# Thermocouple_Amplifier.net
KiCad netlist of a schematic drawn in Altium Designer
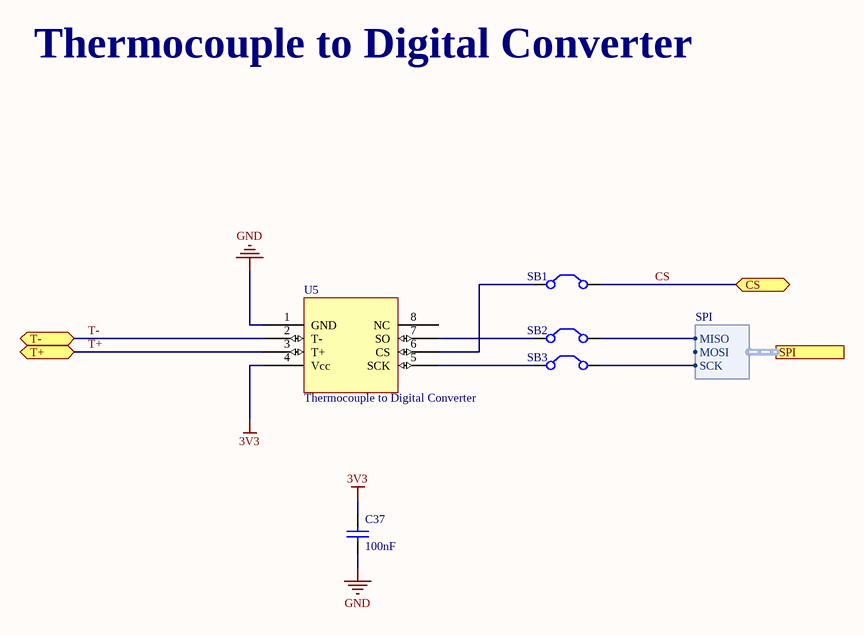
[diagram p0: Thermocouple_Amplifier.SchDoc]

(export (version "E")
  (design (tool "Eeschema 10.0.6"))
  (components
    (comp (ref "C37")
      (value "100nF")
      (footprint "CAP_0603")
      (description "Capacitor")
      (fields (field (name "Comment") "Cap"))
      (libsource (lib "Miscellaneous Devices") (part "Cap"))
    )
    (comp (ref "SB1")
      (value "Solder Bridge")
      (footprint "Solder Bridge")
      (description "Jumper Wire")
      (libsource (lib "Miscellaneous Devices") (part "Jumper"))
    )
    (comp (ref "SB2")
      (value "Solder Bridge")
      (footprint "Solder Bridge")
      (description "Jumper Wire")
      (libsource (lib "Miscellaneous Devices") (part "Jumper"))
    )
    (comp (ref "SB3")
      (value "Solder Bridge")
      (footprint "Solder Bridge")
      (description "Jumper Wire")
      (libsource (lib "Miscellaneous Devices") (part "Jumper"))
    )
    (comp (ref "U5")
      (value "Thermocouple to Digital Converter")
      (footprint "8-SOIC MAXIM")
      (libsource (lib "LaunchyRIOComponents") (part "MAX31855x"))
    )
  )
  (nets
    (net (code "2") (name "/CS") (class "Default")
      (node (ref "SB1") (pin "2") (pinfunction "C2_2") (pintype "passive"))
    )
    (net (code "3") (name "/MISO") (class "Default")
      (node (ref "SB2") (pin "2") (pinfunction "C2_2") (pintype "passive"))
    )
    (net (code "4") (name "/SCK") (class "Default")
      (node (ref "SB3") (pin "2") (pinfunction "C2_2") (pintype "passive"))
    )
    (net (code "5") (name "/T+") (class "Default")
      (node (ref "U5") (pin "3") (pinfunction "T+_3") (pintype "bidirectional"))
    )
    (net (code "6") (name "/T-") (class "Default")
      (node (ref "U5") (pin "2") (pinfunction "T-_2") (pintype "bidirectional"))
    )
    (net (code "8") (name "3V3") (class "Default")
      (node (ref "C37") (pin "2") (pinfunction "2_2") (pintype "passive"))
      (node (ref "U5") (pin "4") (pinfunction "Vcc_4") (pintype "power_in"))
    )
    (net (code "9") (name "GND") (class "Default")
      (node (ref "C37") (pin "1") (pinfunction "1_1") (pintype "passive"))
      (node (ref "U5") (pin "1") (pinfunction "GND_1") (pintype "power_in"))
    )
    (net (code "10") (name "Net-(SB1-C1)") (class "Default")
      (node (ref "SB1") (pin "1") (pinfunction "C1_1") (pintype "passive"))
      (node (ref "U5") (pin "6") (pinfunction "CS_6") (pintype "bidirectional"))
    )
    (net (code "11") (name "Net-(SB2-C1)") (class "Default")
      (node (ref "SB2") (pin "1") (pinfunction "C1_1") (pintype "passive"))
      (node (ref "U5") (pin "7") (pinfunction "SO_7") (pintype "bidirectional"))
    )
    (net (code "12") (name "Net-(SB3-C1)") (class "Default")
      (node (ref "SB3") (pin "1") (pinfunction "C1_1") (pintype "passive"))
      (node (ref "U5") (pin "5") (pinfunction "SCK_5") (pintype "bidirectional"))
    )
    (net (code "13") (name "unconnected-(U5-NC-Pad8)") (class "Default")
      (node (ref "U5") (pin "8") (pinfunction "NC_8") (pintype "passive"))
    )
  )
)
